# Undervoltage.net
KiCad netlist of a schematic drawn in Altium Designer
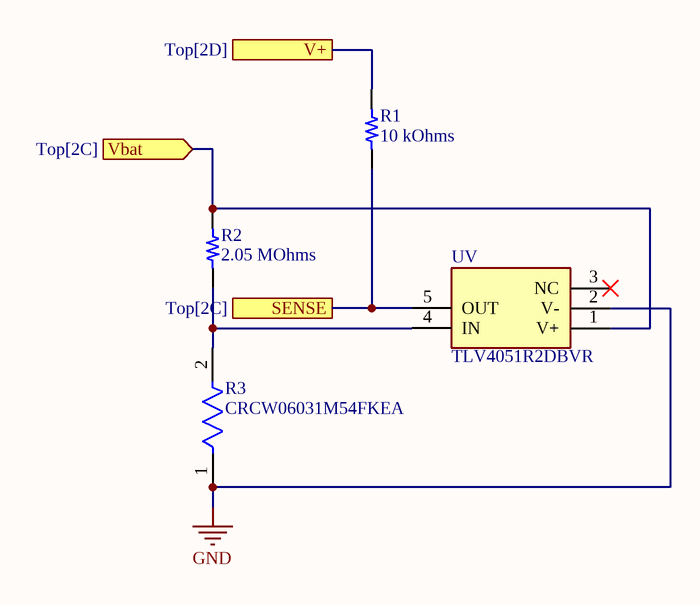
[diagram p0: Undervoltage.SchDoc]

(export (version "E")
  (design (tool "Eeschema 10.0.6"))
  (components
    (comp (ref "R1")
      (value "10 kOhms")
      (footprint "RES 0603_1608")
      (description "RES SMD 10K OHM 0.5% 1/16W 0603")
      (fields (field (name "MANUFACTURER") "Susumu") (field (name "PART NUMBER") "RR0816P-103-D"))
      (libsource (lib "Gopher Motorsports") (part "RESISTOR"))
    )
    (comp (ref "R2")
      (value "2.05 MOhms")
      (footprint "RES 0603_1608")
      (description "RES 2.05M OHM 1% 1/10W 0603")
      (fields
        (field (name "PART NUMBER") "RMCF0603FT2M05")
        (field (name "MANUFACTURER") "Stackpole Electronics Inc")
      )
      (libsource (lib "Gopher Motorsports") (part "RESISTOR"))
    )
    (comp (ref "R3")
      (value "CRCW06031M54FKEA")
      (footprint "FP-CRCW0603-e3-IPC_B")
      (description "RES Thick Film, 1.54MΩ, 1%, 0.1W, 100ppm/°C, 0603")
      (fields (field (name "TOLERANCE") "1%"))
      (libsource (lib "Altium Content Vault") (part "1029c3af85768c4190bb7ad29bc67b5"))
    )
    (comp (ref "UV")
      (value "TLV4051R2DBVR")
      (footprint "SamacSys:SOT95P280X145-5N")
      (description "Integrated Circuit")
      (libsource (lib "*") (part "TLV4051R2DBVR"))
    )
  )
  (nets
    (net (code "1") (name "/SENSE") (class "Default")
      (node (ref "R1") (pin "1") (pinfunction "1_1") (pintype "passive"))
      (node (ref "UV") (pin "5") (pinfunction "OUT_5") (pintype "passive"))
    )
    (net (code "2") (name "/V+") (class "Default")
      (node (ref "R1") (pin "2") (pinfunction "2_2") (pintype "passive"))
    )
    (net (code "3") (name "/Vbat") (class "Default")
      (node (ref "R2") (pin "2") (pinfunction "2_2") (pintype "passive"))
      (node (ref "UV") (pin "1") (pinfunction "V+_1") (pintype "passive"))
    )
    (net (code "4") (name "GND") (class "Default")
      (node (ref "R3") (pin "1") (pinfunction "1_1") (pintype "passive"))
      (node (ref "UV") (pin "2") (pinfunction "V-_2") (pintype "passive"))
    )
    (net (code "5") (name "Net-(UV-IN)") (class "Default")
      (node (ref "R2") (pin "1") (pinfunction "1_1") (pintype "passive"))
      (node (ref "R3") (pin "2") (pinfunction "2_2") (pintype "passive"))
      (node (ref "UV") (pin "4") (pinfunction "IN_4") (pintype "passive"))
    )
    (net (code "6") (name "unconnected-(UV-NC-Pad3)") (class "Default")
      (node (ref "UV") (pin "3") (pinfunction "NC_3") (pintype "passive+no_connect"))
    )
  )
)
